# DriverModule.net
KiCad netlist of a schematic drawn in Altium Designer
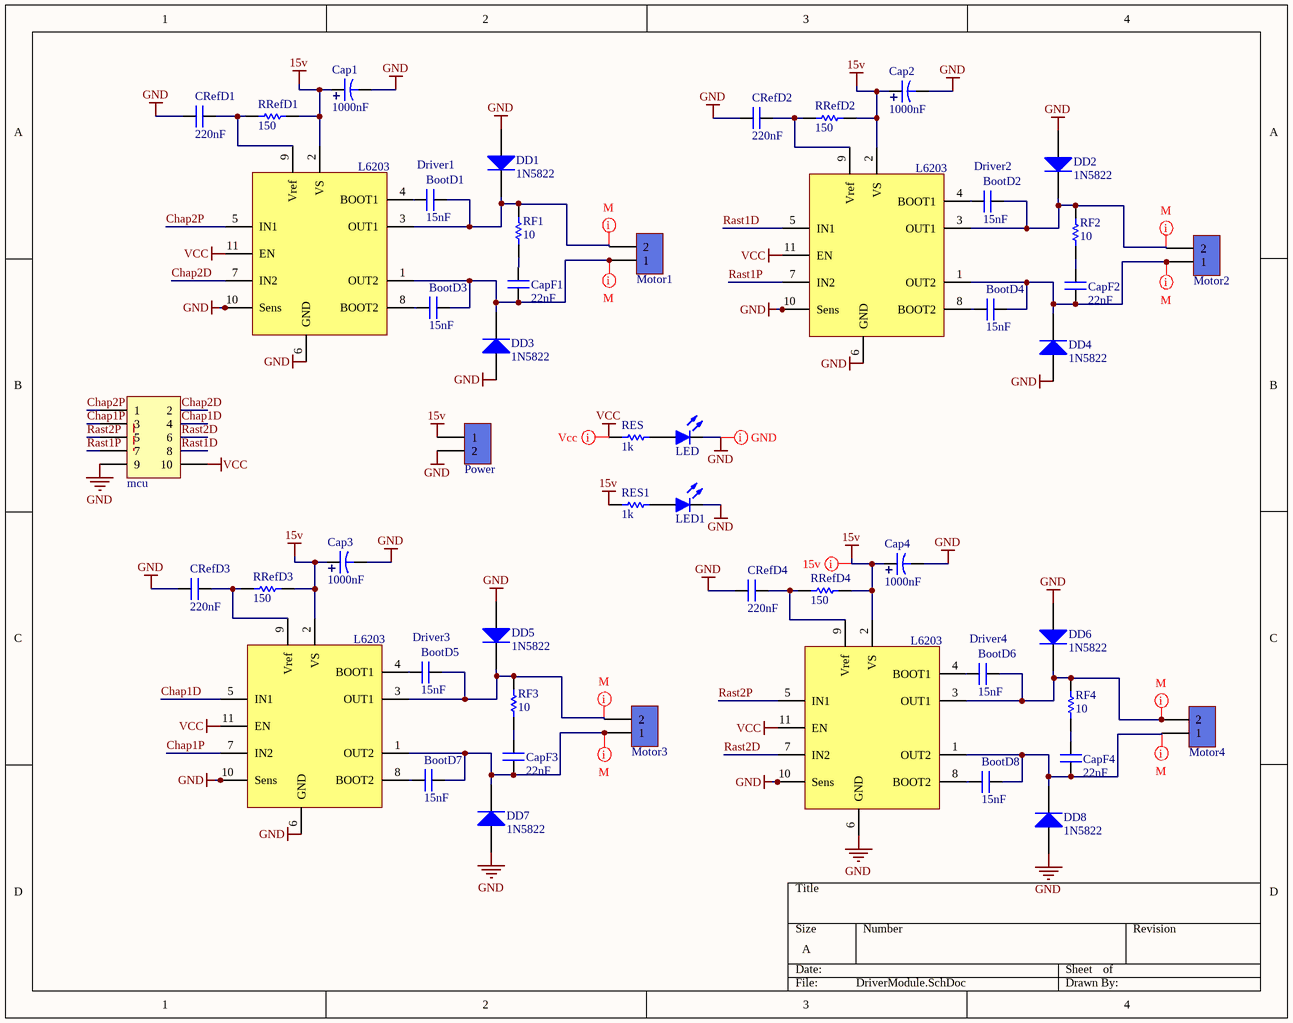
[diagram p0: DriverModule.SchDoc]

(export (version "E")
  (design (tool "Eeschema 10.0.6"))
  (components
    (comp (ref "BootD1")
      (value "15nF")
      (footprint "Cap - 100nF")
      (libsource (lib "Mahmah") (part "CAPACITOR-SMD"))
    )
    (comp (ref "BootD2")
      (value "15nF")
      (footprint "Cap - 100nF")
      (libsource (lib "Mahmah") (part "CAPACITOR-SMD"))
    )
    (comp (ref "BootD3")
      (value "15nF")
      (footprint "Cap - 100nF")
      (libsource (lib "Mahmah") (part "CAPACITOR-SMD"))
    )
    (comp (ref "BootD4")
      (value "15nF")
      (footprint "Cap - 100nF")
      (libsource (lib "Mahmah") (part "CAPACITOR-SMD"))
    )
    (comp (ref "BootD5")
      (value "15nF")
      (footprint "Cap - 100nF")
      (libsource (lib "Mahmah") (part "CAPACITOR-SMD"))
    )
    (comp (ref "BootD6")
      (value "15nF")
      (footprint "Cap - 100nF")
      (libsource (lib "Mahmah") (part "CAPACITOR-SMD"))
    )
    (comp (ref "BootD7")
      (value "15nF")
      (footprint "Cap - 100nF")
      (libsource (lib "Mahmah") (part "CAPACITOR-SMD"))
    )
    (comp (ref "BootD8")
      (value "15nF")
      (footprint "Cap - 100nF")
      (libsource (lib "Mahmah") (part "CAPACITOR-SMD"))
    )
    (comp (ref "Cap1")
      (value "1000nF")
      (footprint "C2200UF-10V_10*16")
      (libsource (lib "") (part "CAPACITOR_1"))
    )
    (comp (ref "Cap2")
      (value "1000nF")
      (footprint "C2200UF-10V_10*16")
      (libsource (lib "Mahmah") (part "CAPACITOR"))
    )
    (comp (ref "Cap3")
      (value "1000nF")
      (footprint "C2200UF-10V_10*16")
      (libsource (lib "") (part "CAPACITOR_1"))
    )
    (comp (ref "Cap4")
      (value "1000nF")
      (footprint "C2200UF-10V_10*16")
      (libsource (lib "Mahmah") (part "CAPACITOR"))
    )
    (comp (ref "CapF1")
      (value "22nF")
      (footprint "Cap - 100nF")
      (libsource (lib "Mahmah") (part "CAPACITOR-SMD"))
    )
    (comp (ref "CapF2")
      (value "22nF")
      (footprint "Cap - 100nF")
      (libsource (lib "Mahmah") (part "CAPACITOR-SMD"))
    )
    (comp (ref "CapF3")
      (value "22nF")
      (footprint "Cap - 100nF")
      (libsource (lib "Mahmah") (part "CAPACITOR-SMD"))
    )
    (comp (ref "CapF4")
      (value "22nF")
      (footprint "Cap - 100nF")
      (libsource (lib "Mahmah") (part "CAPACITOR-SMD"))
    )
    (comp (ref "CRefD1")
      (value "220nF")
      (footprint "Cap - 100nF")
      (libsource (lib "Mahmah") (part "CAPACITOR-SMD"))
    )
    (comp (ref "CRefD2")
      (value "220nF")
      (footprint "Cap - 100nF")
      (libsource (lib "Mahmah") (part "CAPACITOR-SMD"))
    )
    (comp (ref "CRefD3")
      (value "220nF")
      (footprint "Cap - 100nF")
      (libsource (lib "Mahmah") (part "CAPACITOR-SMD"))
    )
    (comp (ref "CRefD4")
      (value "220nF")
      (footprint "Cap - 100nF")
      (libsource (lib "Mahmah") (part "CAPACITOR-SMD"))
    )
    (comp (ref "DD1")
      (value "1N5822")
      (footprint "Diode")
      (description "High Conductance Fast Diode")
      (fields (field (name "PUBLISHER") "Altium Limited"))
      (libsource (lib "Electrovolt Lib") (part "Diode 1N4148"))
    )
    (comp (ref "DD2")
      (value "1N5822")
      (footprint "Diode")
      (description "High Conductance Fast Diode")
      (fields (field (name "PUBLISHER") "Altium Limited"))
      (libsource (lib "Electrovolt Lib") (part "Diode 1N4148"))
    )
    (comp (ref "DD3")
      (value "1N5822")
      (footprint "Diode")
      (description "High Conductance Fast Diode")
      (fields (field (name "PUBLISHER") "Altium Limited"))
      (libsource (lib "Electrovolt Lib") (part "Diode 1N4148"))
    )
    (comp (ref "DD4")
      (value "1N5822")
      (footprint "Diode")
      (description "High Conductance Fast Diode")
      (fields (field (name "PUBLISHER") "Altium Limited"))
      (libsource (lib "Electrovolt Lib") (part "Diode 1N4148"))
    )
    (comp (ref "DD5")
      (value "1N5822")
      (footprint "Diode")
      (description "High Conductance Fast Diode")
      (fields (field (name "PUBLISHER") "Altium Limited"))
      (libsource (lib "Electrovolt Lib") (part "Diode 1N4148"))
    )
    (comp (ref "DD6")
      (value "1N5822")
      (footprint "Diode")
      (description "High Conductance Fast Diode")
      (fields (field (name "PUBLISHER") "Altium Limited"))
      (libsource (lib "Electrovolt Lib") (part "Diode 1N4148"))
    )
    (comp (ref "DD7")
      (value "1N5822")
      (footprint "Diode")
      (description "High Conductance Fast Diode")
      (fields (field (name "PUBLISHER") "Altium Limited"))
      (libsource (lib "Electrovolt Lib") (part "Diode 1N4148"))
    )
    (comp (ref "DD8")
      (value "1N5822")
      (footprint "Diode")
      (description "High Conductance Fast Diode")
      (fields (field (name "PUBLISHER") "Altium Limited"))
      (libsource (lib "Electrovolt Lib") (part "Diode 1N4148"))
    )
    (comp (ref "Driver1")
      (value "L6203")
      (footprint "L6203")
      (description "DMOS FULL BRIDGE DRIVER")
      (fields (field (name "DESIGNER") "Saeid Jorablo"))
      (libsource (lib "Electrovolt Lib") (part "L6203"))
    )
    (comp (ref "Driver2")
      (value "L6203")
      (footprint "L6203")
      (description "DMOS FULL BRIDGE DRIVER")
      (fields (field (name "DESIGNER") "Saeid Jorablo"))
      (libsource (lib "Electrovolt Lib") (part "L6203"))
    )
    (comp (ref "Driver3")
      (value "L6203")
      (footprint "L6203")
      (description "DMOS FULL BRIDGE DRIVER")
      (fields (field (name "DESIGNER") "Saeid Jorablo"))
      (libsource (lib "Electrovolt Lib") (part "L6203"))
    )
    (comp (ref "Driver4")
      (value "L6203")
      (footprint "L6203")
      (description "DMOS FULL BRIDGE DRIVER")
      (fields (field (name "DESIGNER") "Saeid Jorablo"))
      (libsource (lib "Electrovolt Lib") (part "L6203"))
    )
    (comp (ref "LED") (value "LED-SMD") (footprint "0805 LED") (libsource (lib "Mahmah") (part "LED-SMD")))
    (comp (ref "LED1") (value "LED-SMD") (footprint "0805 LED") (libsource (lib "Mahmah") (part "LED-SMD")))
    (comp (ref "mcu")
      (value "CONNECTOR_IDC_5X2")
      (footprint "IDC2.54-10PIN")
      (description "IDC, 5-Pin, Dual row")
      (fields
        (field (name "MANUFACTURER") "CHINA")
        (field (name "PUBLISHER") "ABBAS BASEREH")
        (field (name "DESIGNER") "ABBAS BASEREH")
      )
      (libsource (lib "Altium") (part "IDC 5X2"))
    )
    (comp (ref "Motor1")
      (value "KF301_Terminal")
      (footprint "KF301 2PIN")
      (description "Terminal 2 Pin 250VAC 16A")
      (fields (field (name "DESIGNER") "Abbas Basereh"))
      (libsource (lib "Altium") (part "KF301-2Pin_Terminal"))
    )
    (comp (ref "Motor2")
      (value "KF301_Terminal")
      (footprint "KF301 2PIN")
      (description "Terminal 2 Pin 250VAC 16A")
      (fields (field (name "DESIGNER") "Abbas Basereh"))
      (libsource (lib "Altium") (part "KF301-2Pin_Terminal"))
    )
    (comp (ref "Motor3")
      (value "KF301_Terminal")
      (footprint "KF301 2PIN")
      (description "Terminal 2 Pin 250VAC 16A")
      (fields (field (name "DESIGNER") "Abbas Basereh"))
      (libsource (lib "Altium") (part "KF301-2Pin_Terminal"))
    )
    (comp (ref "Motor4")
      (value "KF301_Terminal")
      (footprint "KF301 2PIN")
      (description "Terminal 2 Pin 250VAC 16A")
      (fields (field (name "DESIGNER") "Abbas Basereh"))
      (libsource (lib "Altium") (part "KF301-2Pin_Terminal"))
    )
    (comp (ref "Power")
      (value "KF301_Terminal")
      (footprint "KF301 2PIN")
      (description "Terminal 2 Pin 250VAC 16A")
      (fields (field (name "DESIGNER") "Abbas Basereh"))
      (libsource (lib "") (part "KF301-2Pin_Terminal_1"))
    )
    (comp (ref "RES") (value "1k") (footprint "1206") (libsource (lib "Mahmah") (part "RESISTOR")))
    (comp (ref "RES1") (value "1k") (footprint "1206") (libsource (lib "Mahmah") (part "RESISTOR")))
    (comp (ref "RF1") (value "10") (footprint "Res-(1/4)") (libsource (lib "Mahmah") (part "RESISTOR")))
    (comp (ref "RF2") (value "10") (footprint "Res-(1/4)") (libsource (lib "Mahmah") (part "RESISTOR")))
    (comp (ref "RF3") (value "10") (footprint "Res-(1/4)") (libsource (lib "Mahmah") (part "RESISTOR")))
    (comp (ref "RF4") (value "10") (footprint "Res-(1/4)") (libsource (lib "Mahmah") (part "RESISTOR")))
    (comp (ref "RRefD1") (value "150") (footprint "Res-(1/4)") (libsource (lib "Mahmah") (part "RESISTOR")))
    (comp (ref "RRefD2") (value "150") (footprint "Res-(1/4)") (libsource (lib "Mahmah") (part "RESISTOR")))
    (comp (ref "RRefD3") (value "150") (footprint "Res-(1/4)") (libsource (lib "Mahmah") (part "RESISTOR")))
    (comp (ref "RRefD4") (value "150") (footprint "Res-(1/4)") (libsource (lib "Mahmah") (part "RESISTOR")))
  )
  (nets
    (net (code "1") (name "/Chap1D") (class "Default")
      (node (ref "Driver3") (pin "5") (pinfunction "IN1_5") (pintype "passive"))
      (node (ref "mcu") (pin "4") (pinfunction "4_4") (pintype "passive"))
    )
    (net (code "2") (name "/Chap1P") (class "Default")
      (node (ref "Driver3") (pin "7") (pinfunction "IN2_7") (pintype "passive"))
      (node (ref "mcu") (pin "3") (pinfunction "3_3") (pintype "passive"))
    )
    (net (code "3") (name "/Chap2D") (class "Default")
      (node (ref "Driver1") (pin "7") (pinfunction "IN2_7") (pintype "passive"))
      (node (ref "mcu") (pin "2") (pinfunction "2_2") (pintype "passive"))
    )
    (net (code "4") (name "/Chap2P") (class "Default")
      (node (ref "Driver1") (pin "5") (pinfunction "IN1_5") (pintype "passive"))
      (node (ref "mcu") (pin "1") (pinfunction "1_1") (pintype "passive"))
    )
    (net (code "5") (name "/Rast1D") (class "Default")
      (node (ref "Driver2") (pin "5") (pinfunction "IN1_5") (pintype "passive"))
      (node (ref "mcu") (pin "8") (pinfunction "8_8") (pintype "passive"))
    )
    (net (code "6") (name "/Rast1P") (class "Default")
      (node (ref "Driver2") (pin "7") (pinfunction "IN2_7") (pintype "passive"))
      (node (ref "mcu") (pin "7") (pinfunction "7_7") (pintype "passive"))
    )
    (net (code "7") (name "/Rast2D") (class "Default")
      (node (ref "Driver4") (pin "7") (pinfunction "IN2_7") (pintype "passive"))
      (node (ref "mcu") (pin "6") (pinfunction "6_6") (pintype "passive"))
    )
    (net (code "8") (name "/Rast2P") (class "Default")
      (node (ref "Driver4") (pin "5") (pinfunction "IN1_5") (pintype "passive"))
      (node (ref "mcu") (pin "5") (pinfunction "5_5") (pintype "passive"))
    )
    (net (code "9") (name "15v") (class "Default")
      (node (ref "Cap1") (pin "1") (pinfunction "1_1") (pintype "passive"))
      (node (ref "Cap2") (pin "1") (pinfunction "1_1") (pintype "passive"))
      (node (ref "Cap3") (pin "1") (pinfunction "1_1") (pintype "passive"))
      (node (ref "Cap4") (pin "1") (pinfunction "1_1") (pintype "passive"))
      (node (ref "Driver1") (pin "2") (pinfunction "VS_2") (pintype "passive"))
      (node (ref "Driver2") (pin "2") (pinfunction "VS_2") (pintype "passive"))
      (node (ref "Driver3") (pin "2") (pinfunction "VS_2") (pintype "passive"))
      (node (ref "Driver4") (pin "2") (pinfunction "VS_2") (pintype "passive"))
      (node (ref "Power") (pin "1") (pinfunction "1_1") (pintype "passive"))
      (node (ref "RES1") (pin "1") (pinfunction "1_1") (pintype "passive"))
      (node (ref "RRefD1") (pin "2") (pinfunction "2_2") (pintype "passive"))
      (node (ref "RRefD2") (pin "2") (pinfunction "2_2") (pintype "passive"))
      (node (ref "RRefD3") (pin "2") (pinfunction "2_2") (pintype "passive"))
      (node (ref "RRefD4") (pin "2") (pinfunction "2_2") (pintype "passive"))
    )
    (net (code "10") (name "GND") (class "Default")
      (node (ref "CRefD1") (pin "2") (pinfunction "-_2") (pintype "passive"))
      (node (ref "CRefD2") (pin "2") (pinfunction "-_2") (pintype "passive"))
      (node (ref "CRefD3") (pin "2") (pinfunction "-_2") (pintype "passive"))
      (node (ref "CRefD4") (pin "2") (pinfunction "-_2") (pintype "passive"))
      (node (ref "Cap1") (pin "2") (pinfunction "-_2") (pintype "passive"))
      (node (ref "Cap2") (pin "2") (pinfunction "-_2") (pintype "passive"))
      (node (ref "Cap3") (pin "2") (pinfunction "-_2") (pintype "passive"))
      (node (ref "Cap4") (pin "2") (pinfunction "-_2") (pintype "passive"))
      (node (ref "DD1") (pin "1") (pinfunction "A_1") (pintype "passive"))
      (node (ref "DD2") (pin "1") (pinfunction "A_1") (pintype "passive"))
      (node (ref "DD3") (pin "1") (pinfunction "A_1") (pintype "passive"))
      (node (ref "DD4") (pin "1") (pinfunction "A_1") (pintype "passive"))
      (node (ref "DD5") (pin "1") (pinfunction "A_1") (pintype "passive"))
      (node (ref "DD6") (pin "1") (pinfunction "A_1") (pintype "passive"))
      (node (ref "DD7") (pin "1") (pinfunction "A_1") (pintype "passive"))
      (node (ref "DD8") (pin "1") (pinfunction "A_1") (pintype "passive"))
      (node (ref "Driver1") (pin "10") (pinfunction "Sens_10") (pintype "passive"))
      (node (ref "Driver1") (pin "6") (pinfunction "GND_6") (pintype "passive"))
      (node (ref "Driver2") (pin "10") (pinfunction "Sens_10") (pintype "passive"))
      (node (ref "Driver2") (pin "6") (pinfunction "GND_6") (pintype "passive"))
      (node (ref "Driver3") (pin "10") (pinfunction "Sens_10") (pintype "passive"))
      (node (ref "Driver3") (pin "6") (pinfunction "GND_6") (pintype "passive"))
      (node (ref "Driver4") (pin "10") (pinfunction "Sens_10") (pintype "passive"))
      (node (ref "Driver4") (pin "6") (pinfunction "GND_6") (pintype "passive"))
      (node (ref "LED") (pin "2") (pinfunction "2_2") (pintype "passive"))
      (node (ref "LED1") (pin "2") (pinfunction "2_2") (pintype "passive"))
      (node (ref "Power") (pin "2") (pinfunction "2_2") (pintype "passive"))
      (node (ref "mcu") (pin "9") (pinfunction "9_9") (pintype "passive"))
    )
    (net (code "11") (name "Net-(BootD1--)") (class "Default")
      (node (ref "BootD1") (pin "2") (pinfunction "-_2") (pintype "passive"))
      (node (ref "Driver1") (pin "4") (pinfunction "BOOT1_4") (pintype "passive"))
    )
    (net (code "12") (name "Net-(BootD2--)") (class "Default")
      (node (ref "BootD2") (pin "2") (pinfunction "-_2") (pintype "passive"))
      (node (ref "Driver2") (pin "4") (pinfunction "BOOT1_4") (pintype "passive"))
    )
    (net (code "13") (name "Net-(BootD3--)") (class "Default")
      (node (ref "BootD3") (pin "2") (pinfunction "-_2") (pintype "passive"))
      (node (ref "CapF1") (pin "1") (pinfunction "1_1") (pintype "passive"))
      (node (ref "DD3") (pin "2") (pinfunction "K_2") (pintype "passive"))
      (node (ref "Driver1") (pin "1") (pinfunction "OUT2_1") (pintype "passive"))
      (node (ref "Motor1") (pin "1") (pinfunction "1_1") (pintype "passive"))
    )
    (net (code "14") (name "Net-(BootD4--)") (class "Default")
      (node (ref "BootD4") (pin "2") (pinfunction "-_2") (pintype "passive"))
      (node (ref "CapF2") (pin "1") (pinfunction "1_1") (pintype "passive"))
      (node (ref "DD4") (pin "2") (pinfunction "K_2") (pintype "passive"))
      (node (ref "Driver2") (pin "1") (pinfunction "OUT2_1") (pintype "passive"))
      (node (ref "Motor2") (pin "1") (pinfunction "1_1") (pintype "passive"))
    )
    (net (code "15") (name "Net-(BootD5--)") (class "Default")
      (node (ref "BootD5") (pin "2") (pinfunction "-_2") (pintype "passive"))
      (node (ref "Driver3") (pin "4") (pinfunction "BOOT1_4") (pintype "passive"))
    )
    (net (code "16") (name "Net-(BootD6--)") (class "Default")
      (node (ref "BootD6") (pin "2") (pinfunction "-_2") (pintype "passive"))
      (node (ref "Driver4") (pin "4") (pinfunction "BOOT1_4") (pintype "passive"))
    )
    (net (code "17") (name "Net-(BootD7--)") (class "Default")
      (node (ref "BootD7") (pin "2") (pinfunction "-_2") (pintype "passive"))
      (node (ref "CapF3") (pin "1") (pinfunction "1_1") (pintype "passive"))
      (node (ref "DD7") (pin "2") (pinfunction "K_2") (pintype "passive"))
      (node (ref "Driver3") (pin "1") (pinfunction "OUT2_1") (pintype "passive"))
      (node (ref "Motor3") (pin "1") (pinfunction "1_1") (pintype "passive"))
    )
    (net (code "18") (name "Net-(BootD8--)") (class "Default")
      (node (ref "BootD8") (pin "2") (pinfunction "-_2") (pintype "passive"))
      (node (ref "CapF4") (pin "1") (pinfunction "1_1") (pintype "passive"))
      (node (ref "DD8") (pin "2") (pinfunction "K_2") (pintype "passive"))
      (node (ref "Driver4") (pin "1") (pinfunction "OUT2_1") (pintype "passive"))
      (node (ref "Motor4") (pin "1") (pinfunction "1_1") (pintype "passive"))
    )
    (net (code "19") (name "Net-(CapF1--)") (class "Default")
      (node (ref "CapF1") (pin "2") (pinfunction "-_2") (pintype "passive"))
      (node (ref "RF1") (pin "1") (pinfunction "1_1") (pintype "passive"))
    )
    (net (code "20") (name "Net-(CapF2--)") (class "Default")
      (node (ref "CapF2") (pin "2") (pinfunction "-_2") (pintype "passive"))
      (node (ref "RF2") (pin "1") (pinfunction "1_1") (pintype "passive"))
    )
    (net (code "21") (name "Net-(CapF3--)") (class "Default")
      (node (ref "CapF3") (pin "2") (pinfunction "-_2") (pintype "passive"))
      (node (ref "RF3") (pin "1") (pinfunction "1_1") (pintype "passive"))
    )
    (net (code "22") (name "Net-(CapF4--)") (class "Default")
      (node (ref "CapF4") (pin "2") (pinfunction "-_2") (pintype "passive"))
      (node (ref "RF4") (pin "1") (pinfunction "1_1") (pintype "passive"))
    )
    (net (code "23") (name "Net-(DD1-K)") (class "Default")
      (node (ref "BootD1") (pin "1") (pinfunction "1_1") (pintype "passive"))
      (node (ref "DD1") (pin "2") (pinfunction "K_2") (pintype "passive"))
      (node (ref "Driver1") (pin "3") (pinfunction "OUT1_3") (pintype "passive"))
      (node (ref "Motor1") (pin "2") (pinfunction "2_2") (pintype "passive"))
      (node (ref "RF1") (pin "2") (pinfunction "2_2") (pintype "passive"))
    )
    (net (code "24") (name "Net-(DD2-K)") (class "Default")
      (node (ref "BootD2") (pin "1") (pinfunction "1_1") (pintype "passive"))
      (node (ref "DD2") (pin "2") (pinfunction "K_2") (pintype "passive"))
      (node (ref "Driver2") (pin "3") (pinfunction "OUT1_3") (pintype "passive"))
      (node (ref "Motor2") (pin "2") (pinfunction "2_2") (pintype "passive"))
      (node (ref "RF2") (pin "2") (pinfunction "2_2") (pintype "passive"))
    )
    (net (code "25") (name "Net-(DD5-K)") (class "Default")
      (node (ref "BootD5") (pin "1") (pinfunction "1_1") (pintype "passive"))
      (node (ref "DD5") (pin "2") (pinfunction "K_2") (pintype "passive"))
      (node (ref "Driver3") (pin "3") (pinfunction "OUT1_3") (pintype "passive"))
      (node (ref "Motor3") (pin "2") (pinfunction "2_2") (pintype "passive"))
      (node (ref "RF3") (pin "2") (pinfunction "2_2") (pintype "passive"))
    )
    (net (code "26") (name "Net-(DD6-K)") (class "Default")
      (node (ref "BootD6") (pin "1") (pinfunction "1_1") (pintype "passive"))
      (node (ref "DD6") (pin "2") (pinfunction "K_2") (pintype "passive"))
      (node (ref "Driver4") (pin "3") (pinfunction "OUT1_3") (pintype "passive"))
      (node (ref "Motor4") (pin "2") (pinfunction "2_2") (pintype "passive"))
      (node (ref "RF4") (pin "2") (pinfunction "2_2") (pintype "passive"))
    )
    (net (code "27") (name "Net-(Driver1-BOOT2)") (class "Default")
      (node (ref "BootD3") (pin "1") (pinfunction "1_1") (pintype "passive"))
      (node (ref "Driver1") (pin "8") (pinfunction "BOOT2_8") (pintype "passive"))
    )
    (net (code "28") (name "Net-(Driver1-Vref)") (class "Default")
      (node (ref "CRefD1") (pin "1") (pinfunction "1_1") (pintype "passive"))
      (node (ref "Driver1") (pin "9") (pinfunction "Vref_9") (pintype "passive"))
      (node (ref "RRefD1") (pin "1") (pinfunction "1_1") (pintype "passive"))
    )
    (net (code "29") (name "Net-(Driver2-BOOT2)") (class "Default")
      (node (ref "BootD4") (pin "1") (pinfunction "1_1") (pintype "passive"))
      (node (ref "Driver2") (pin "8") (pinfunction "BOOT2_8") (pintype "passive"))
    )
    (net (code "30") (name "Net-(Driver2-Vref)") (class "Default")
      (node (ref "CRefD2") (pin "1") (pinfunction "1_1") (pintype "passive"))
      (node (ref "Driver2") (pin "9") (pinfunction "Vref_9") (pintype "passive"))
      (node (ref "RRefD2") (pin "1") (pinfunction "1_1") (pintype "passive"))
    )
    (net (code "31") (name "Net-(Driver3-BOOT2)") (class "Default")
      (node (ref "BootD7") (pin "1") (pinfunction "1_1") (pintype "passive"))
      (node (ref "Driver3") (pin "8") (pinfunction "BOOT2_8") (pintype "passive"))
    )
    (net (code "32") (name "Net-(Driver3-Vref)") (class "Default")
      (node (ref "CRefD3") (pin "1") (pinfunction "1_1") (pintype "passive"))
      (node (ref "Driver3") (pin "9") (pinfunction "Vref_9") (pintype "passive"))
      (node (ref "RRefD3") (pin "1") (pinfunction "1_1") (pintype "passive"))
    )
    (net (code "33") (name "Net-(Driver4-BOOT2)") (class "Default")
      (node (ref "BootD8") (pin "1") (pinfunction "1_1") (pintype "passive"))
      (node (ref "Driver4") (pin "8") (pinfunction "BOOT2_8") (pintype "passive"))
    )
    (net (code "34") (name "Net-(Driver4-Vref)") (class "Default")
      (node (ref "CRefD4") (pin "1") (pinfunction "1_1") (pintype "passive"))
      (node (ref "Driver4") (pin "9") (pinfunction "Vref_9") (pintype "passive"))
      (node (ref "RRefD4") (pin "1") (pinfunction "1_1") (pintype "passive"))
    )
    (net (code "35") (name "Net-(LED-Pad1)") (class "Default")
      (node (ref "LED") (pin "1") (pinfunction "1_1") (pintype "passive"))
      (node (ref "RES") (pin "2") (pinfunction "2_2") (pintype "passive"))
    )
    (net (code "36") (name "Net-(LED1-Pad1)") (class "Default")
      (node (ref "LED1") (pin "1") (pinfunction "1_1") (pintype "passive"))
      (node (ref "RES1") (pin "2") (pinfunction "2_2") (pintype "passive"))
    )
    (net (code "37") (name "VCC") (class "Default")
      (node (ref "Driver1") (pin "11") (pinfunction "EN_11") (pintype "passive"))
      (node (ref "Driver2") (pin "11") (pinfunction "EN_11") (pintype "passive"))
      (node (ref "Driver3") (pin "11") (pinfunction "EN_11") (pintype "passive"))
      (node (ref "Driver4") (pin "11") (pinfunction "EN_11") (pintype "passive"))
      (node (ref "RES") (pin "1") (pinfunction "1_1") (pintype "passive"))
      (node (ref "mcu") (pin "10") (pinfunction "10_10") (pintype "passive"))
    )
  )
)
